# ETAPA_DE_SALIDA.net
KiCad netlist of a schematic drawn in Altium Designer
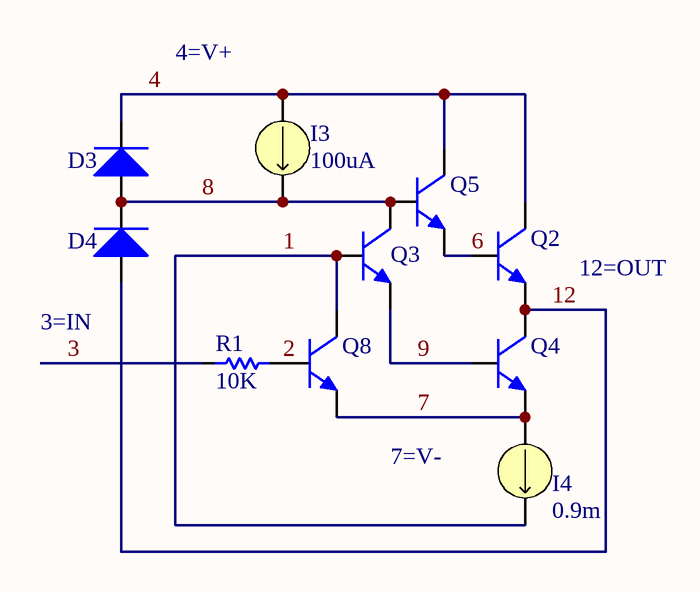
[diagram p0: ETAPA DE SALIDA.SCHDOC]

(export (version "E")
  (design (tool "Eeschema 10.0.6"))
  (components
    (comp (ref "D3")
      (value "Diode")
      (footprint "diode400")
      (description "Diodo")
      (libsource (lib "FEDE") (part "Diode"))
    )
    (comp (ref "D4")
      (value "Diode")
      (footprint "diode400")
      (description "Diodo")
      (libsource (lib "FEDE") (part "Diode"))
    )
    (comp (ref "I3")
      (value "100uA")
      (description "Current Source")
      (fields (field (name "Comment") "ISRC") (field (name "PUBLISHER") "Altium Limited"))
      (libsource (lib "Simulation Sources") (part "ISRC"))
    )
    (comp (ref "I4")
      (value "0.9m")
      (description "Current Source")
      (fields (field (name "Comment") "ISRC") (field (name "PUBLISHER") "Altium Limited"))
      (libsource (lib "Simulation Sources") (part "ISRC"))
    )
    (comp (ref "Q2")
      (value "NPN")
      (footprint "SOT23")
      (description "NPN Bipolar Transistor")
      (libsource (lib "FEDE") (part "NPN"))
    )
    (comp (ref "Q3")
      (value "NPN")
      (footprint "SOT23")
      (description "NPN Bipolar Transistor")
      (libsource (lib "FEDE") (part "NPN"))
    )
    (comp (ref "Q4")
      (value "NPN")
      (footprint "SOT23")
      (description "NPN Bipolar Transistor")
      (libsource (lib "FEDE") (part "NPN"))
    )
    (comp (ref "Q5")
      (value "NPN")
      (footprint "SOT23")
      (description "NPN Bipolar Transistor")
      (libsource (lib "FEDE") (part "NPN"))
    )
    (comp (ref "Q8")
      (value "NPN")
      (footprint "SOT23")
      (description "NPN Bipolar Transistor")
      (libsource (lib "FEDE") (part "NPN"))
    )
    (comp (ref "R1")
      (value "10K")
      (footprint "0805")
      (description "Resistor")
      (fields (field (name "POWER") "0.25W") (field (name "Comment") "Res"))
      (libsource (lib "FEDE") (part "Res"))
    )
  )
  (nets
    (net (code "1") (name "/1") (class "Default")
      (node (ref "I4") (pin "2") (pinfunction "2_2") (pintype "passive"))
      (node (ref "Q3") (pin "2") (pinfunction "B_2") (pintype "passive"))
      (node (ref "Q8") (pin "1") (pinfunction "C_1") (pintype "passive"))
    )
    (net (code "2") (name "/2") (class "Default")
      (node (ref "Q8") (pin "2") (pinfunction "B_2") (pintype "passive"))
      (node (ref "R1") (pin "1") (pinfunction "1_1") (pintype "passive"))
    )
    (net (code "3") (name "/3") (class "Default")
      (node (ref "R1") (pin "2") (pinfunction "2_2") (pintype "passive"))
    )
    (net (code "4") (name "/4") (class "Default")
      (node (ref "D3") (pin "2") (pinfunction "2_2") (pintype "passive"))
      (node (ref "I3") (pin "1") (pinfunction "1_1") (pintype "passive"))
      (node (ref "Q2") (pin "1") (pinfunction "C_1") (pintype "passive"))
      (node (ref "Q5") (pin "1") (pinfunction "C_1") (pintype "passive"))
    )
    (net (code "5") (name "/6") (class "Default")
      (node (ref "Q2") (pin "2") (pinfunction "B_2") (pintype "passive"))
      (node (ref "Q5") (pin "3") (pinfunction "E_3") (pintype "passive"))
    )
    (net (code "6") (name "/7") (class "Default")
      (node (ref "I4") (pin "1") (pinfunction "1_1") (pintype "passive"))
      (node (ref "Q4") (pin "3") (pinfunction "E_3") (pintype "passive"))
      (node (ref "Q8") (pin "3") (pinfunction "E_3") (pintype "passive"))
    )
    (net (code "7") (name "/8") (class "Default")
      (node (ref "D3") (pin "1") (pinfunction "1_1") (pintype "passive"))
      (node (ref "D4") (pin "2") (pinfunction "2_2") (pintype "passive"))
      (node (ref "I3") (pin "2") (pinfunction "2_2") (pintype "passive"))
      (node (ref "Q3") (pin "1") (pinfunction "C_1") (pintype "passive"))
      (node (ref "Q5") (pin "2") (pinfunction "B_2") (pintype "passive"))
    )
    (net (code "8") (name "/9") (class "Default")
      (node (ref "Q3") (pin "3") (pinfunction "E_3") (pintype "passive"))
      (node (ref "Q4") (pin "2") (pinfunction "B_2") (pintype "passive"))
    )
    (net (code "9") (name "/12") (class "Default")
      (node (ref "D4") (pin "1") (pinfunction "1_1") (pintype "passive"))
      (node (ref "Q2") (pin "3") (pinfunction "E_3") (pintype "passive"))
      (node (ref "Q4") (pin "1") (pinfunction "C_1") (pintype "passive"))
    )
  )
)
